# axiom_beta_interface_cmv12000_v0_3.net
KiCad netlist of a schematic drawn in EAGLE
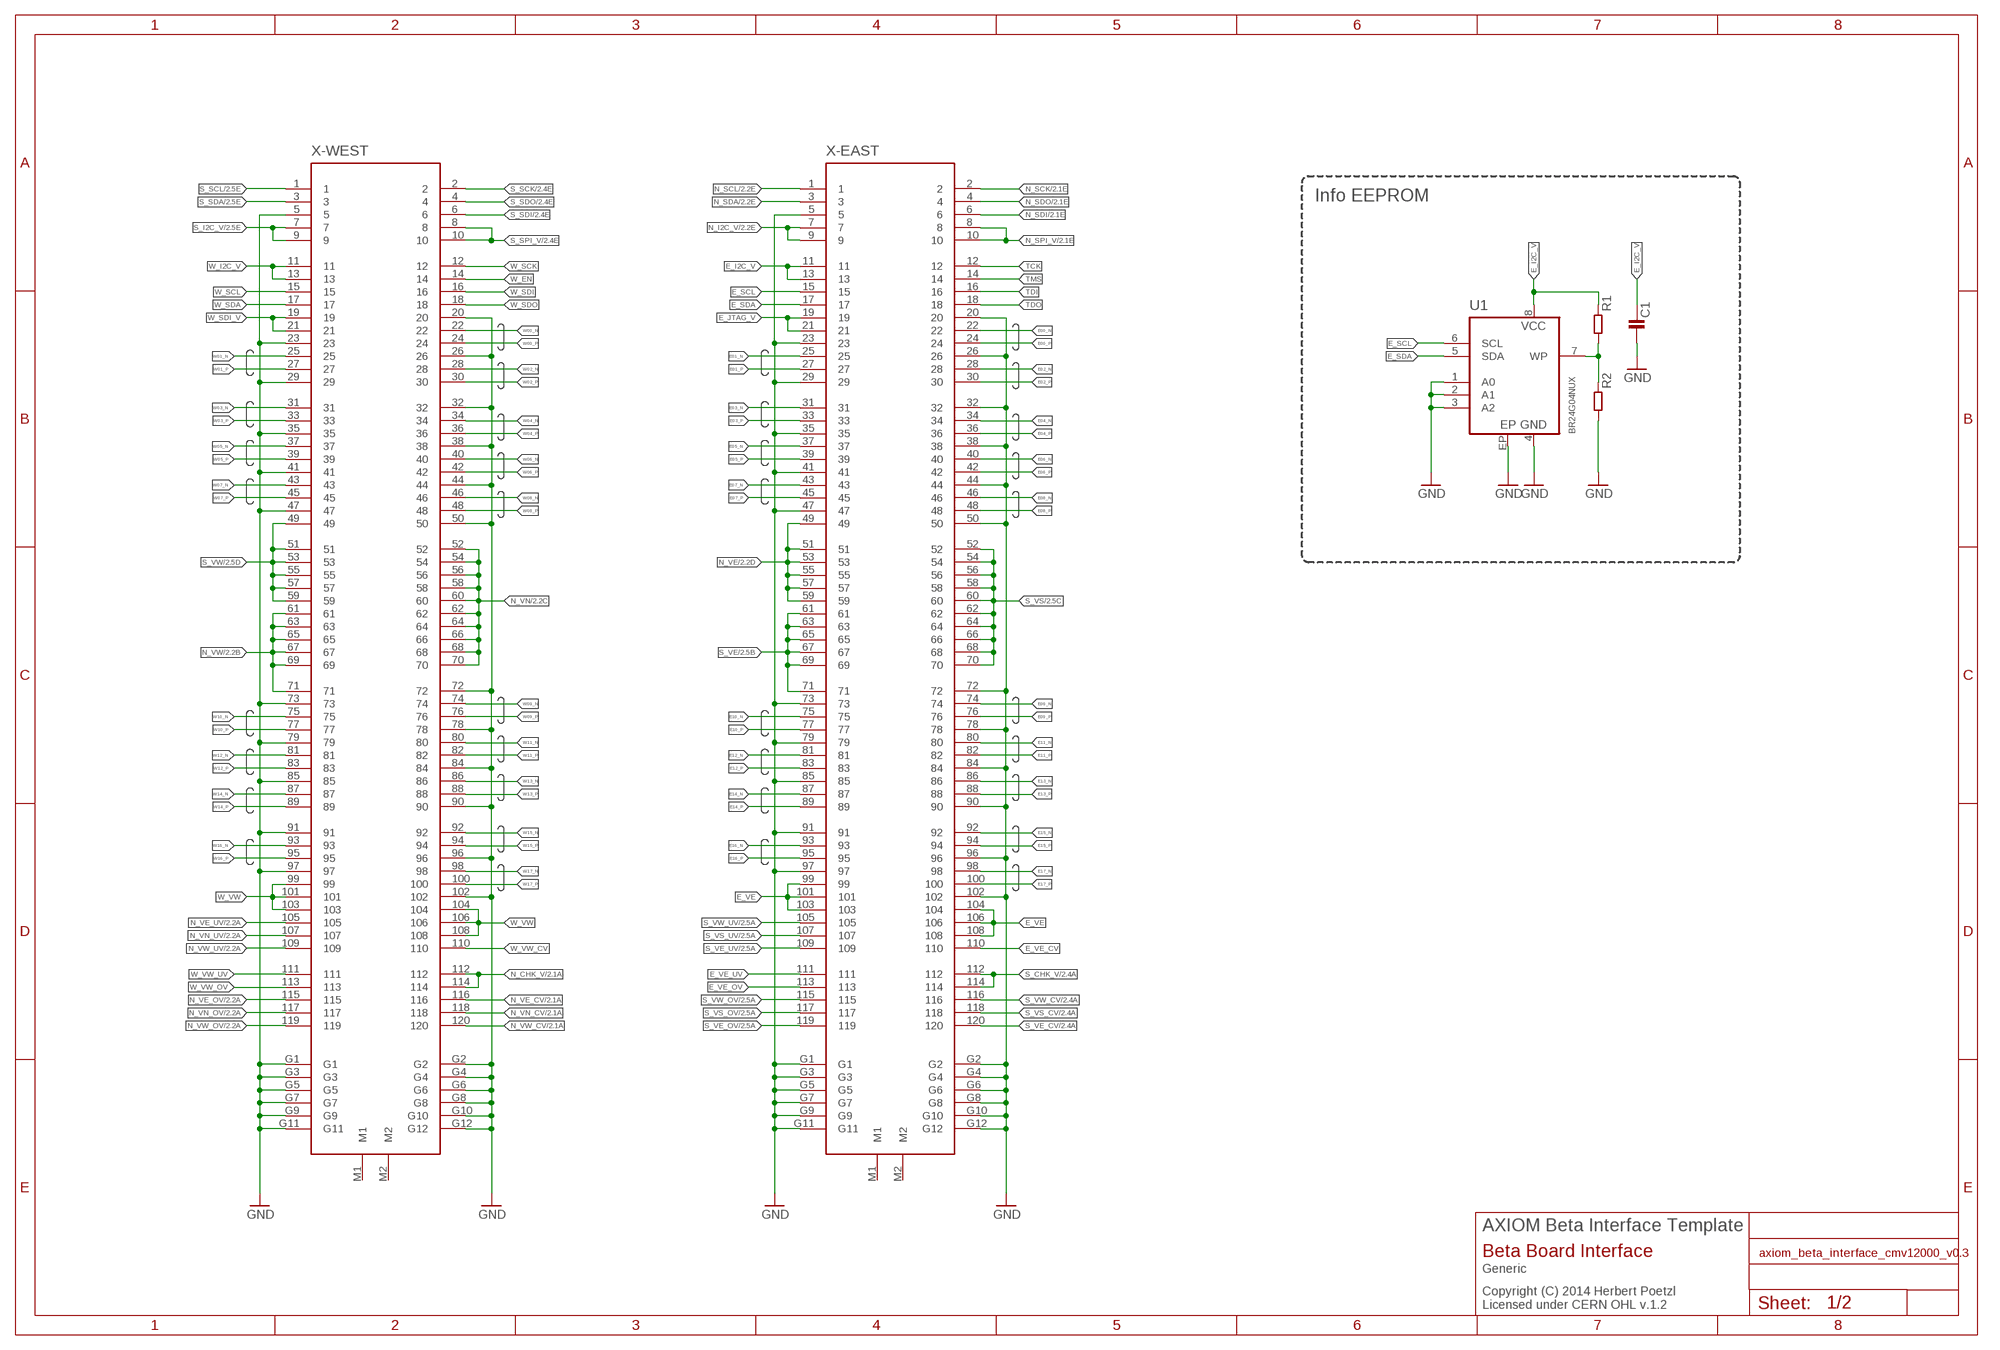
[diagram p0: schematic, sheet 1]
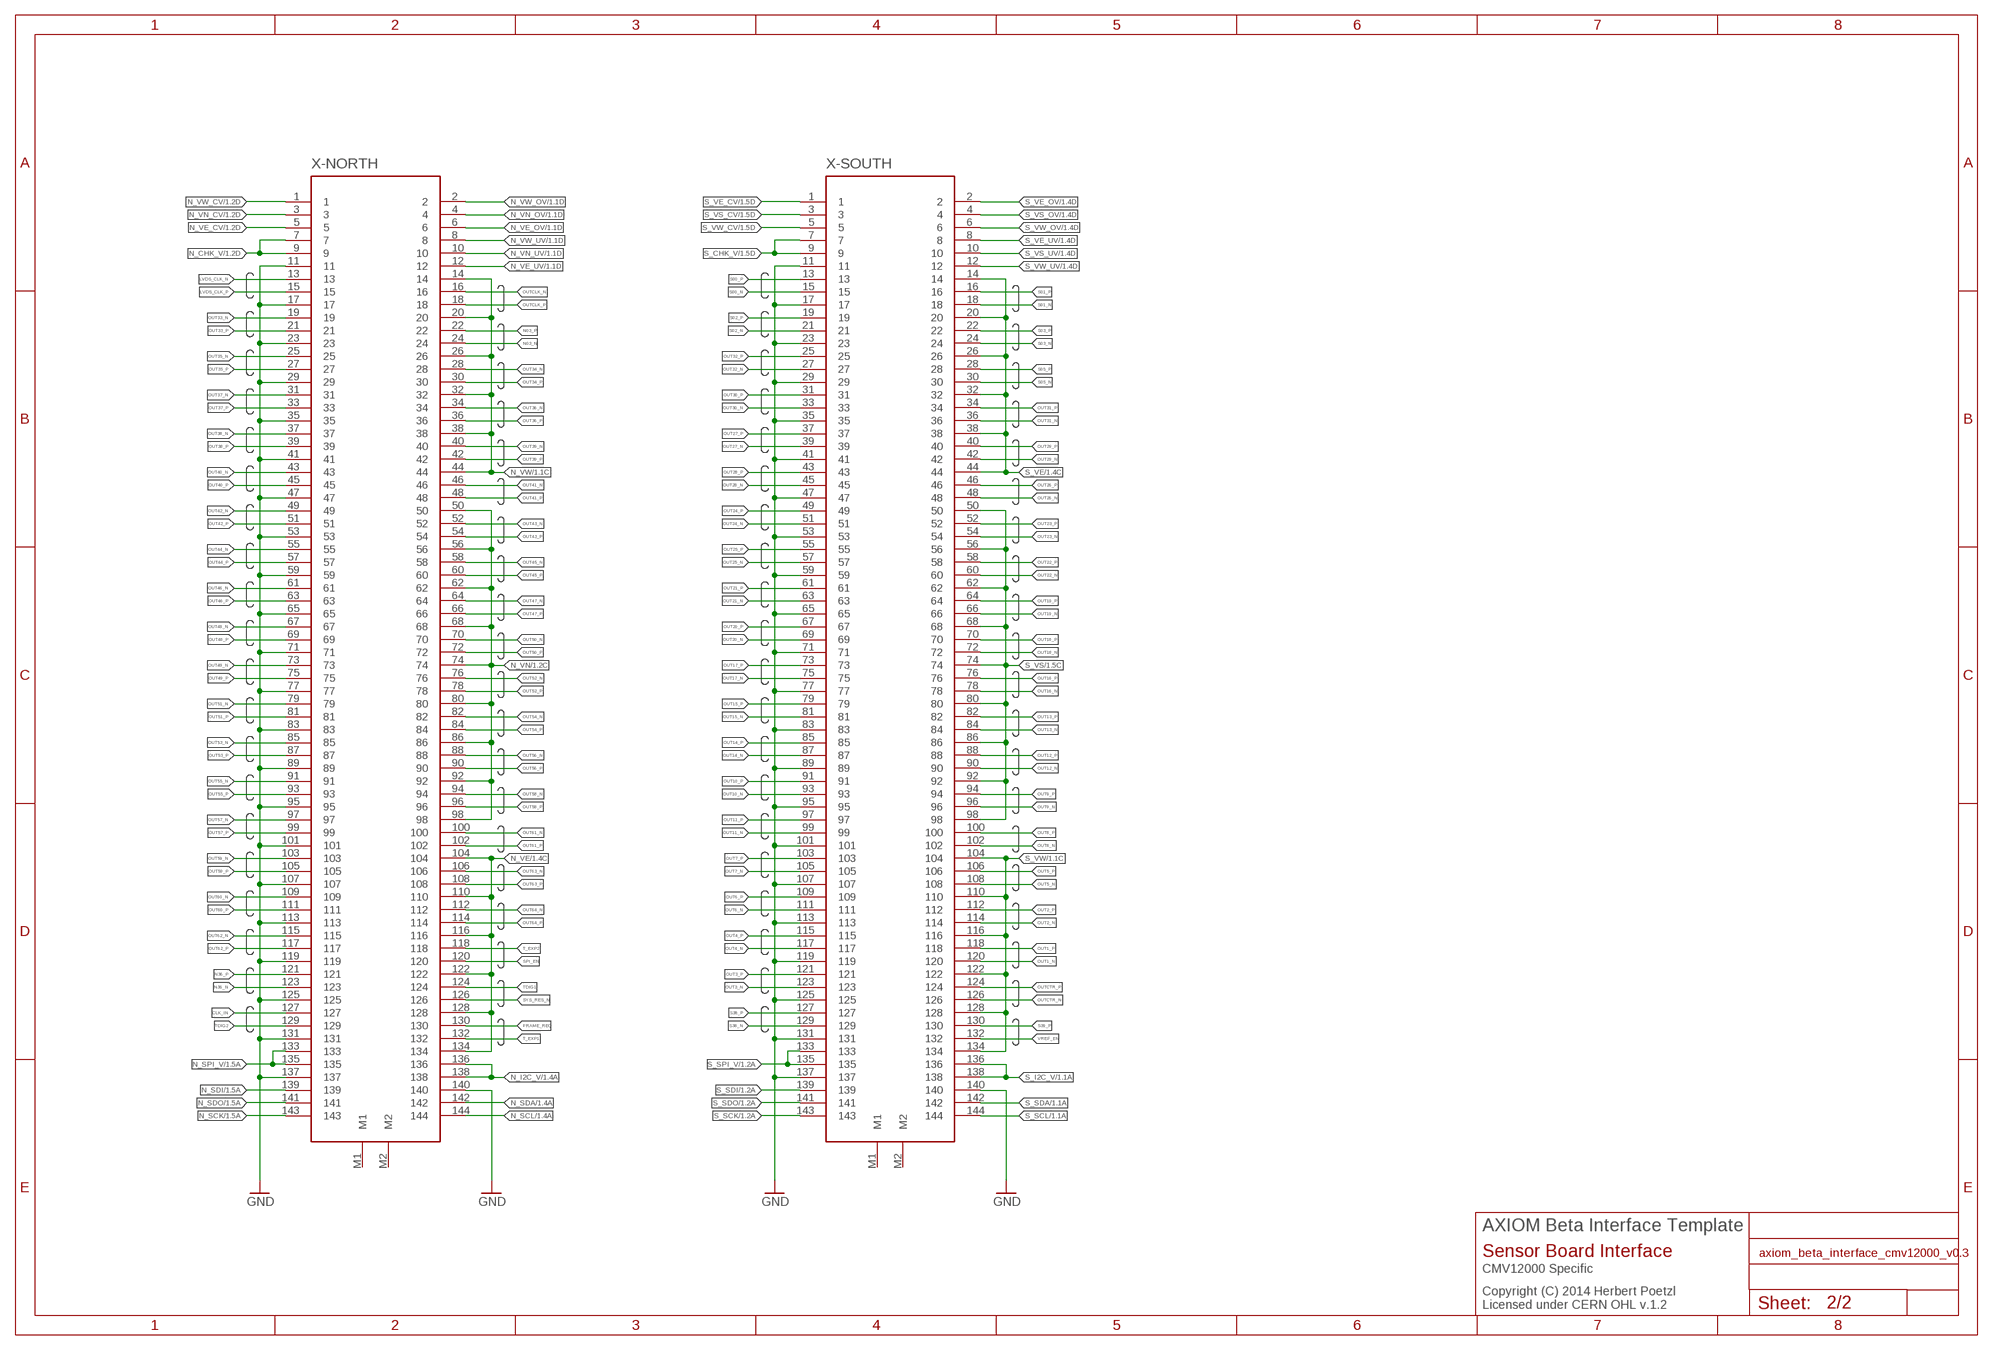
[diagram p1: schematic, sheet 2]

(export (version "E")
  (design (tool "Eeschema 10.0.6"))
  (components
    (comp (ref "X-NORTH")
      (value "FX10-144S")
      (footprint "eagle-import:FX10A-144S")
      (libsource (lib "eagle-import") (part "FX10-144S"))
    )
    (comp (ref "X-SOUTH")
      (value "FX10-144S")
      (footprint "eagle-import:FX10A-144S")
      (libsource (lib "eagle-import") (part "FX10-144S"))
    )
    (comp (ref "C1")
      (value "C0402-B")
      (footprint "eagle-import:0402-B")
      (libsource (lib "eagle-import") (part "C0402-B"))
    )
    (comp (ref "R1")
      (value "R0402-B")
      (footprint "eagle-import:0402-B")
      (libsource (lib "eagle-import") (part "R0402-B"))
    )
    (comp (ref "R2")
      (value "R0402-B")
      (footprint "eagle-import:0402-B")
      (libsource (lib "eagle-import") (part "R0402-B"))
    )
    (comp (ref "U1")
      (value "BR24G04NUX")
      (footprint "eagle-import:DFN200X300X100-9N")
      (libsource (lib "eagle-import") (part "BR24G04NUX"))
    )
    (comp (ref "X-EAST")
      (value "FX10-120/12P")
      (footprint "eagle-import:FX10A-120P_12")
      (libsource (lib "eagle-import") (part "FX10-120/12P"))
    )
    (comp (ref "X-WEST")
      (value "FX10-120/12P")
      (footprint "eagle-import:FX10A-120P_12")
      (libsource (lib "eagle-import") (part "FX10-120/12P"))
    )
  )
  (nets
    (net (code "1") (name "CLK_IN") (class "Default")
      (node (ref "X-NORTH") (pin "127") (pinfunction "127_127") (pintype "bidirectional"))
    )
    (net (code "2") (name "E00_N") (class "Default")
      (node (ref "X-EAST") (pin "22") (pinfunction "22_22") (pintype "bidirectional"))
    )
    (net (code "3") (name "E00_P") (class "Default")
      (node (ref "X-EAST") (pin "24") (pinfunction "24_24") (pintype "bidirectional"))
    )
    (net (code "4") (name "E01_N") (class "Default")
      (node (ref "X-EAST") (pin "25") (pinfunction "25_25") (pintype "bidirectional"))
    )
    (net (code "5") (name "E01_P") (class "Default")
      (node (ref "X-EAST") (pin "27") (pinfunction "27_27") (pintype "bidirectional"))
    )
    (net (code "6") (name "E02_N") (class "Default")
      (node (ref "X-EAST") (pin "28") (pinfunction "28_28") (pintype "bidirectional"))
    )
    (net (code "7") (name "E02_P") (class "Default")
      (node (ref "X-EAST") (pin "30") (pinfunction "30_30") (pintype "bidirectional"))
    )
    (net (code "8") (name "E03_N") (class "Default")
      (node (ref "X-EAST") (pin "31") (pinfunction "31_31") (pintype "bidirectional"))
    )
    (net (code "9") (name "E03_P") (class "Default")
      (node (ref "X-EAST") (pin "33") (pinfunction "33_33") (pintype "bidirectional"))
    )
    (net (code "10") (name "E04_N") (class "Default")
      (node (ref "X-EAST") (pin "34") (pinfunction "34_34") (pintype "bidirectional"))
    )
    (net (code "11") (name "E04_P") (class "Default")
      (node (ref "X-EAST") (pin "36") (pinfunction "36_36") (pintype "bidirectional"))
    )
    (net (code "12") (name "E05_N") (class "Default")
      (node (ref "X-EAST") (pin "37") (pinfunction "37_37") (pintype "bidirectional"))
    )
    (net (code "13") (name "E05_P") (class "Default")
      (node (ref "X-EAST") (pin "39") (pinfunction "39_39") (pintype "bidirectional"))
    )
    (net (code "14") (name "E06_N") (class "Default")
      (node (ref "X-EAST") (pin "40") (pinfunction "40_40") (pintype "bidirectional"))
    )
    (net (code "15") (name "E06_P") (class "Default")
      (node (ref "X-EAST") (pin "42") (pinfunction "42_42") (pintype "bidirectional"))
    )
    (net (code "16") (name "E07_N") (class "Default")
      (node (ref "X-EAST") (pin "43") (pinfunction "43_43") (pintype "bidirectional"))
    )
    (net (code "17") (name "E07_P") (class "Default")
      (node (ref "X-EAST") (pin "45") (pinfunction "45_45") (pintype "bidirectional"))
    )
    (net (code "18") (name "E08_N") (class "Default")
      (node (ref "X-EAST") (pin "46") (pinfunction "46_46") (pintype "bidirectional"))
    )
    (net (code "19") (name "E08_P") (class "Default")
      (node (ref "X-EAST") (pin "48") (pinfunction "48_48") (pintype "bidirectional"))
    )
    (net (code "20") (name "E09_N") (class "Default")
      (node (ref "X-EAST") (pin "74") (pinfunction "74_74") (pintype "bidirectional"))
    )
    (net (code "21") (name "E09_P") (class "Default")
      (node (ref "X-EAST") (pin "76") (pinfunction "76_76") (pintype "bidirectional"))
    )
    (net (code "22") (name "E10_N") (class "Default")
      (node (ref "X-EAST") (pin "75") (pinfunction "75_75") (pintype "bidirectional"))
    )
    (net (code "23") (name "E10_P") (class "Default")
      (node (ref "X-EAST") (pin "77") (pinfunction "77_77") (pintype "bidirectional"))
    )
    (net (code "24") (name "E11_N") (class "Default")
      (node (ref "X-EAST") (pin "80") (pinfunction "80_80") (pintype "bidirectional"))
    )
    (net (code "25") (name "E11_P") (class "Default")
      (node (ref "X-EAST") (pin "82") (pinfunction "82_82") (pintype "bidirectional"))
    )
    (net (code "26") (name "E12_N") (class "Default")
      (node (ref "X-EAST") (pin "81") (pinfunction "81_81") (pintype "bidirectional"))
    )
    (net (code "27") (name "E12_P") (class "Default")
      (node (ref "X-EAST") (pin "83") (pinfunction "83_83") (pintype "bidirectional"))
    )
    (net (code "28") (name "E13_N") (class "Default")
      (node (ref "X-EAST") (pin "86") (pinfunction "86_86") (pintype "bidirectional"))
    )
    (net (code "29") (name "E13_P") (class "Default")
      (node (ref "X-EAST") (pin "88") (pinfunction "88_88") (pintype "bidirectional"))
    )
    (net (code "30") (name "E14_N") (class "Default")
      (node (ref "X-EAST") (pin "87") (pinfunction "87_87") (pintype "bidirectional"))
    )
    (net (code "31") (name "E14_P") (class "Default")
      (node (ref "X-EAST") (pin "89") (pinfunction "89_89") (pintype "bidirectional"))
    )
    (net (code "32") (name "E15_N") (class "Default")
      (node (ref "X-EAST") (pin "92") (pinfunction "92_92") (pintype "bidirectional"))
    )
    (net (code "33") (name "E15_P") (class "Default")
      (node (ref "X-EAST") (pin "94") (pinfunction "94_94") (pintype "bidirectional"))
    )
    (net (code "34") (name "E16_N") (class "Default")
      (node (ref "X-EAST") (pin "93") (pinfunction "93_93") (pintype "bidirectional"))
    )
    (net (code "35") (name "E16_P") (class "Default")
      (node (ref "X-EAST") (pin "95") (pinfunction "95_95") (pintype "bidirectional"))
    )
    (net (code "36") (name "E17_N") (class "Default")
      (node (ref "X-EAST") (pin "98") (pinfunction "98_98") (pintype "bidirectional"))
    )
    (net (code "37") (name "E17_P") (class "Default")
      (node (ref "X-EAST") (pin "100") (pinfunction "100_100") (pintype "bidirectional"))
    )
    (net (code "38") (name "E_I2C_V") (class "Default")
      (node (ref "C1") (pin "1") (pinfunction "1_1") (pintype "passive"))
      (node (ref "R1") (pin "1") (pinfunction "1_1") (pintype "passive"))
      (node (ref "U1") (pin "8") (pinfunction "VCC_8") (pintype "power_in"))
      (node (ref "X-EAST") (pin "11") (pinfunction "11_11") (pintype "bidirectional"))
      (node (ref "X-EAST") (pin "13") (pinfunction "13_13") (pintype "bidirectional"))
    )
    (net (code "39") (name "E_JTAG_V") (class "Default")
      (node (ref "X-EAST") (pin "19") (pinfunction "19_19") (pintype "bidirectional"))
      (node (ref "X-EAST") (pin "21") (pinfunction "21_21") (pintype "bidirectional"))
    )
    (net (code "40") (name "E_SCL") (class "Default")
      (node (ref "U1") (pin "6") (pinfunction "SCL_6") (pintype "input"))
      (node (ref "X-EAST") (pin "15") (pinfunction "15_15") (pintype "bidirectional"))
    )
    (net (code "41") (name "E_SDA") (class "Default")
      (node (ref "U1") (pin "5") (pinfunction "SDA_5") (pintype "bidirectional"))
      (node (ref "X-EAST") (pin "17") (pinfunction "17_17") (pintype "bidirectional"))
    )
    (net (code "42") (name "E_VE") (class "Default")
      (node (ref "X-EAST") (pin "101") (pinfunction "101_101") (pintype "bidirectional"))
      (node (ref "X-EAST") (pin "103") (pinfunction "103_103") (pintype "bidirectional"))
      (node (ref "X-EAST") (pin "104") (pinfunction "104_104") (pintype "bidirectional"))
      (node (ref "X-EAST") (pin "106") (pinfunction "106_106") (pintype "bidirectional"))
      (node (ref "X-EAST") (pin "108") (pinfunction "108_108") (pintype "bidirectional"))
      (node (ref "X-EAST") (pin "99") (pinfunction "99_99") (pintype "bidirectional"))
    )
    (net (code "43") (name "E_VE_CV") (class "Default")
      (node (ref "X-EAST") (pin "110") (pinfunction "110_110") (pintype "bidirectional"))
    )
    (net (code "44") (name "E_VE_OV") (class "Default")
      (node (ref "X-EAST") (pin "113") (pinfunction "113_113") (pintype "bidirectional"))
    )
    (net (code "45") (name "E_VE_UV") (class "Default")
      (node (ref "X-EAST") (pin "111") (pinfunction "111_111") (pintype "bidirectional"))
    )
    (net (code "46") (name "FRAME_REQ") (class "Default")
      (node (ref "X-NORTH") (pin "130") (pinfunction "130_130") (pintype "bidirectional"))
    )
    (net (code "47") (name "GND") (class "Default")
      (node (ref "C1") (pin "2") (pinfunction "2_2") (pintype "passive"))
      (node (ref "R2") (pin "2") (pinfunction "2_2") (pintype "passive"))
      (node (ref "U1") (pin "1") (pinfunction "A0_1") (pintype "input"))
      (node (ref "U1") (pin "2") (pinfunction "A1_2") (pintype "input"))
      (node (ref "U1") (pin "3") (pinfunction "A2_3") (pintype "input"))
      (node (ref "U1") (pin "4") (pinfunction "GND_4") (pintype "passive"))
      (node (ref "U1") (pin "EP") (pinfunction "EP_EP") (pintype "passive"))
      (node (ref "X-EAST") (pin "102") (pinfunction "102_102") (pintype "bidirectional"))
      (node (ref "X-EAST") (pin "20") (pinfunction "20_20") (pintype "bidirectional"))
      (node (ref "X-EAST") (pin "23") (pinfunction "23_23") (pintype "bidirectional"))
      (node (ref "X-EAST") (pin "26") (pinfunction "26_26") (pintype "bidirectional"))
      (node (ref "X-EAST") (pin "29") (pinfunction "29_29") (pintype "bidirectional"))
      (node (ref "X-EAST") (pin "32") (pinfunction "32_32") (pintype "bidirectional"))
      (node (ref "X-EAST") (pin "35") (pinfunction "35_35") (pintype "bidirectional"))
      (node (ref "X-EAST") (pin "38") (pinfunction "38_38") (pintype "bidirectional"))
      (node (ref "X-EAST") (pin "41") (pinfunction "41_41") (pintype "bidirectional"))
      (node (ref "X-EAST") (pin "44") (pinfunction "44_44") (pintype "bidirectional"))
      (node (ref "X-EAST") (pin "47") (pinfunction "47_47") (pintype "bidirectional"))
      (node (ref "X-EAST") (pin "5") (pinfunction "5_5") (pintype "bidirectional"))
      (node (ref "X-EAST") (pin "50") (pinfunction "50_50") (pintype "bidirectional"))
      (node (ref "X-EAST") (pin "72") (pinfunction "72_72") (pintype "bidirectional"))
      (node (ref "X-EAST") (pin "73") (pinfunction "73_73") (pintype "bidirectional"))
      (node (ref "X-EAST") (pin "78") (pinfunction "78_78") (pintype "bidirectional"))
      (node (ref "X-EAST") (pin "79") (pinfunction "79_79") (pintype "bidirectional"))
      (node (ref "X-EAST") (pin "84") (pinfunction "84_84") (pintype "bidirectional"))
      (node (ref "X-EAST") (pin "85") (pinfunction "85_85") (pintype "bidirectional"))
      (node (ref "X-EAST") (pin "90") (pinfunction "90_90") (pintype "bidirectional"))
      (node (ref "X-EAST") (pin "91") (pinfunction "91_91") (pintype "bidirectional"))
      (node (ref "X-EAST") (pin "96") (pinfunction "96_96") (pintype "bidirectional"))
      (node (ref "X-EAST") (pin "97") (pinfunction "97_97") (pintype "bidirectional"))
      (node (ref "X-EAST") (pin "G1") (pinfunction "G1_G1") (pintype "bidirectional"))
      (node (ref "X-EAST") (pin "G10") (pinfunction "G10_G10") (pintype "bidirectional"))
      (node (ref "X-EAST") (pin "G11") (pinfunction "G11_G11") (pintype "bidirectional"))
      (node (ref "X-EAST") (pin "G12") (pinfunction "G12_G12") (pintype "bidirectional"))
      (node (ref "X-EAST") (pin "G2") (pinfunction "G2_G2") (pintype "bidirectional"))
      (node (ref "X-EAST") (pin "G3") (pinfunction "G3_G3") (pintype "bidirectional"))
      (node (ref "X-EAST") (pin "G4") (pinfunction "G4_G4") (pintype "bidirectional"))
      (node (ref "X-EAST") (pin "G5") (pinfunction "G5_G5") (pintype "bidirectional"))
      (node (ref "X-EAST") (pin "G6") (pinfunction "G6_G6") (pintype "bidirectional"))
      (node (ref "X-EAST") (pin "G7") (pinfunction "G7_G7") (pintype "bidirectional"))
      (node (ref "X-EAST") (pin "G8") (pinfunction "G8_G8") (pintype "bidirectional"))
      (node (ref "X-EAST") (pin "G9") (pinfunction "G9_G9") (pintype "bidirectional"))
      (node (ref "X-NORTH") (pin "101") (pinfunction "101_101") (pintype "bidirectional"))
      (node (ref "X-NORTH") (pin "107") (pinfunction "107_107") (pintype "bidirectional"))
      (node (ref "X-NORTH") (pin "11") (pinfunction "11_11") (pintype "bidirectional"))
      (node (ref "X-NORTH") (pin "113") (pinfunction "113_113") (pintype "bidirectional"))
      (node (ref "X-NORTH") (pin "119") (pinfunction "119_119") (pintype "bidirectional"))
      (node (ref "X-NORTH") (pin "125") (pinfunction "125_125") (pintype "bidirectional"))
      (node (ref "X-NORTH") (pin "131") (pinfunction "131_131") (pintype "bidirectional"))
      (node (ref "X-NORTH") (pin "137") (pinfunction "137_137") (pintype "bidirectional"))
      (node (ref "X-NORTH") (pin "140") (pinfunction "140_140") (pintype "bidirectional"))
      (node (ref "X-NORTH") (pin "17") (pinfunction "17_17") (pintype "bidirectional"))
      (node (ref "X-NORTH") (pin "23") (pinfunction "23_23") (pintype "bidirectional"))
      (node (ref "X-NORTH") (pin "29") (pinfunction "29_29") (pintype "bidirectional"))
      (node (ref "X-NORTH") (pin "35") (pinfunction "35_35") (pintype "bidirectional"))
      (node (ref "X-NORTH") (pin "41") (pinfunction "41_41") (pintype "bidirectional"))
      (node (ref "X-NORTH") (pin "47") (pinfunction "47_47") (pintype "bidirectional"))
      (node (ref "X-NORTH") (pin "53") (pinfunction "53_53") (pintype "bidirectional"))
      (node (ref "X-NORTH") (pin "59") (pinfunction "59_59") (pintype "bidirectional"))
      (node (ref "X-NORTH") (pin "65") (pinfunction "65_65") (pintype "bidirectional"))
      (node (ref "X-NORTH") (pin "71") (pinfunction "71_71") (pintype "bidirectional"))
      (node (ref "X-NORTH") (pin "77") (pinfunction "77_77") (pintype "bidirectional"))
      (node (ref "X-NORTH") (pin "83") (pinfunction "83_83") (pintype "bidirectional"))
      (node (ref "X-NORTH") (pin "89") (pinfunction "89_89") (pintype "bidirectional"))
      (node (ref "X-NORTH") (pin "95") (pinfunction "95_95") (pintype "bidirectional"))
      (node (ref "X-SOUTH") (pin "101") (pinfunction "101_101") (pintype "bidirectional"))
      (node (ref "X-SOUTH") (pin "107") (pinfunction "107_107") (pintype "bidirectional"))
      (node (ref "X-SOUTH") (pin "11") (pinfunction "11_11") (pintype "bidirectional"))
      (node (ref "X-SOUTH") (pin "113") (pinfunction "113_113") (pintype "bidirectional"))
      (node (ref "X-SOUTH") (pin "119") (pinfunction "119_119") (pintype "bidirectional"))
      (node (ref "X-SOUTH") (pin "125") (pinfunction "125_125") (pintype "bidirectional"))
      (node (ref "X-SOUTH") (pin "131") (pinfunction "131_131") (pintype "bidirectional"))
      (node (ref "X-SOUTH") (pin "137") (pinfunction "137_137") (pintype "bidirectional"))
      (node (ref "X-SOUTH") (pin "140") (pinfunction "140_140") (pintype "bidirectional"))
      (node (ref "X-SOUTH") (pin "17") (pinfunction "17_17") (pintype "bidirectional"))
      (node (ref "X-SOUTH") (pin "23") (pinfunction "23_23") (pintype "bidirectional"))
      (node (ref "X-SOUTH") (pin "29") (pinfunction "29_29") (pintype "bidirectional"))
      (node (ref "X-SOUTH") (pin "35") (pinfunction "35_35") (pintype "bidirectional"))
      (node (ref "X-SOUTH") (pin "41") (pinfunction "41_41") (pintype "bidirectional"))
      (node (ref "X-SOUTH") (pin "47") (pinfunction "47_47") (pintype "bidirectional"))
      (node (ref "X-SOUTH") (pin "53") (pinfunction "53_53") (pintype "bidirectional"))
      (node (ref "X-SOUTH") (pin "59") (pinfunction "59_59") (pintype "bidirectional"))
      (node (ref "X-SOUTH") (pin "65") (pinfunction "65_65") (pintype "bidirectional"))
      (node (ref "X-SOUTH") (pin "71") (pinfunction "71_71") (pintype "bidirectional"))
      (node (ref "X-SOUTH") (pin "77") (pinfunction "77_77") (pintype "bidirectional"))
      (node (ref "X-SOUTH") (pin "83") (pinfunction "83_83") (pintype "bidirectional"))
      (node (ref "X-SOUTH") (pin "89") (pinfunction "89_89") (pintype "bidirectional"))
      (node (ref "X-SOUTH") (pin "95") (pinfunction "95_95") (pintype "bidirectional"))
      (node (ref "X-WEST") (pin "102") (pinfunction "102_102") (pintype "bidirectional"))
      (node (ref "X-WEST") (pin "20") (pinfunction "20_20") (pintype "bidirectional"))
      (node (ref "X-WEST") (pin "23") (pinfunction "23_23") (pintype "bidirectional"))
      (node (ref "X-WEST") (pin "26") (pinfunction "26_26") (pintype "bidirectional"))
      (node (ref "X-WEST") (pin "29") (pinfunction "29_29") (pintype "bidirectional"))
      (node (ref "X-WEST") (pin "32") (pinfunction "32_32") (pintype "bidirectional"))
      (node (ref "X-WEST") (pin "35") (pinfunction "35_35") (pintype "bidirectional"))
      (node (ref "X-WEST") (pin "38") (pinfunction "38_38") (pintype "bidirectional"))
      (node (ref "X-WEST") (pin "41") (pinfunction "41_41") (pintype "bidirectional"))
      (node (ref "X-WEST") (pin "44") (pinfunction "44_44") (pintype "bidirectional"))
      (node (ref "X-WEST") (pin "47") (pinfunction "47_47") (pintype "bidirectional"))
      (node (ref "X-WEST") (pin "5") (pinfunction "5_5") (pintype "bidirectional"))
      (node (ref "X-WEST") (pin "50") (pinfunction "50_50") (pintype "bidirectional"))
      (node (ref "X-WEST") (pin "72") (pinfunction "72_72") (pintype "bidirectional"))
      (node (ref "X-WEST") (pin "73") (pinfunction "73_73") (pintype "bidirectional"))
      (node (ref "X-WEST") (pin "78") (pinfunction "78_78") (pintype "bidirectional"))
      (node (ref "X-WEST") (pin "79") (pinfunction "79_79") (pintype "bidirectional"))
      (node (ref "X-WEST") (pin "84") (pinfunction "84_84") (pintype "bidirectional"))
      (node (ref "X-WEST") (pin "85") (pinfunction "85_85") (pintype "bidirectional"))
      (node (ref "X-WEST") (pin "90") (pinfunction "90_90") (pintype "bidirectional"))
      (node (ref "X-WEST") (pin "91") (pinfunction "91_91") (pintype "bidirectional"))
      (node (ref "X-WEST") (pin "96") (pinfunction "96_96") (pintype "bidirectional"))
      (node (ref "X-WEST") (pin "97") (pinfunction "97_97") (pintype "bidirectional"))
      (node (ref "X-WEST") (pin "G1") (pinfunction "G1_G1") (pintype "bidirectional"))
      (node (ref "X-WEST") (pin "G10") (pinfunction "G10_G10") (pintype "bidirectional"))
      (node (ref "X-WEST") (pin "G11") (pinfunction "G11_G11") (pintype "bidirectional"))
      (node (ref "X-WEST") (pin "G12") (pinfunction "G12_G12") (pintype "bidirectional"))
      (node (ref "X-WEST") (pin "G2") (pinfunction "G2_G2") (pintype "bidirectional"))
      (node (ref "X-WEST") (pin "G3") (pinfunction "G3_G3") (pintype "bidirectional"))
      (node (ref "X-WEST") (pin "G4") (pinfunction "G4_G4") (pintype "bidirectional"))
      (node (ref "X-WEST") (pin "G5") (pinfunction "G5_G5") (pintype "bidirectional"))
      (node (ref "X-WEST") (pin "G6") (pinfunction "G6_G6") (pintype "bidirectional"))
      (node (ref "X-WEST") (pin "G7") (pinfunction "G7_G7") (pintype "bidirectional"))
      (node (ref "X-WEST") (pin "G8") (pinfunction "G8_G8") (pintype "bidirectional"))
      (node (ref "X-WEST") (pin "G9") (pinfunction "G9_G9") (pintype "bidirectional"))
    )
    (net (code "48") (name "LVDS_CLK_N") (class "Default")
      (node (ref "X-NORTH") (pin "13") (pinfunction "13_13") (pintype "bidirectional"))
    )
    (net (code "49") (name "LVDS_CLK_P") (class "Default")
      (node (ref "X-NORTH") (pin "15") (pinfunction "15_15") (pintype "bidirectional"))
    )
    (net (code "50") (name "N03_N") (class "Default")
      (node (ref "X-NORTH") (pin "24") (pinfunction "24_24") (pintype "bidirectional"))
    )
    (net (code "51") (name "N03_P") (class "Default")
      (node (ref "X-NORTH") (pin "22") (pinfunction "22_22") (pintype "bidirectional"))
    )
    (net (code "52") (name "N36_N") (class "Default")
      (node (ref "X-NORTH") (pin "123") (pinfunction "123_123") (pintype "bidirectional"))
    )
    (net (code "53") (name "N36_P") (class "Default")
      (node (ref "X-NORTH") (pin "121") (pinfunction "121_121") (pintype "bidirectional"))
    )
    (net (code "54") (name "N_CHK_V") (class "Default")
      (node (ref "X-NORTH") (pin "7") (pinfunction "7_7") (pintype "bidirectional"))
      (node (ref "X-NORTH") (pin "9") (pinfunction "9_9") (pintype "bidirectional"))
      (node (ref "X-WEST") (pin "112") (pinfunction "112_112") (pintype "bidirectional"))
      (node (ref "X-WEST") (pin "114") (pinfunction "114_114") (pintype "bidirectional"))
    )
    (net (code "55") (name "N_I2C_V") (class "Default")
      (node (ref "X-EAST") (pin "7") (pinfunction "7_7") (pintype "bidirectional"))
      (node (ref "X-EAST") (pin "9") (pinfunction "9_9") (pintype "bidirectional"))
      (node (ref "X-NORTH") (pin "136") (pinfunction "136_136") (pintype "bidirectional"))
      (node (ref "X-NORTH") (pin "138") (pinfunction "138_138") (pintype "bidirectional"))
    )
    (net (code "56") (name "N_SCK") (class "Default")
      (node (ref "X-EAST") (pin "2") (pinfunction "2_2") (pintype "bidirectional"))
      (node (ref "X-NORTH") (pin "143") (pinfunction "143_143") (pintype "bidirectional"))
    )
    (net (code "57") (name "N_SCL") (class "Default")
      (node (ref "X-EAST") (pin "1") (pinfunction "1_1") (pintype "bidirectional"))
      (node (ref "X-NORTH") (pin "144") (pinfunction "144_144") (pintype "bidirectional"))
    )
    (net (code "58") (name "N_SDA") (class "Default")
      (node (ref "X-EAST") (pin "3") (pinfunction "3_3") (pintype "bidirectional"))
      (node (ref "X-NORTH") (pin "142") (pinfunction "142_142") (pintype "bidirectional"))
    )
    (net (code "59") (name "N_SDI") (class "Default")
      (node (ref "X-EAST") (pin "6") (pinfunction "6_6") (pintype "bidirectional"))
      (node (ref "X-NORTH") (pin "139") (pinfunction "139_139") (pintype "bidirectional"))
    )
    (net (code "60") (name "N_SDO") (class "Default")
      (node (ref "X-EAST") (pin "4") (pinfunction "4_4") (pintype "bidirectional"))
      (node (ref "X-NORTH") (pin "141") (pinfunction "141_141") (pintype "bidirectional"))
    )
    (net (code "61") (name "N_SPI_V") (class "Default")
      (node (ref "X-EAST") (pin "10") (pinfunction "10_10") (pintype "bidirectional"))
      (node (ref "X-EAST") (pin "8") (pinfunction "8_8") (pintype "bidirectional"))
      (node (ref "X-NORTH") (pin "133") (pinfunction "133_133") (pintype "bidirectional"))
      (node (ref "X-NORTH") (pin "135") (pinfunction "135_135") (pintype "bidirectional"))
    )
    (net (code "62") (name "N_VE") (class "Default")
      (node (ref "X-EAST") (pin "49") (pinfunction "49_49") (pintype "bidirectional"))
      (node (ref "X-EAST") (pin "51") (pinfunction "51_51") (pintype "bidirectional"))
      (node (ref "X-EAST") (pin "53") (pinfunction "53_53") (pintype "bidirectional"))
      (node (ref "X-EAST") (pin "55") (pinfunction "55_55") (pintype "bidirectional"))
      (node (ref "X-EAST") (pin "57") (pinfunction "57_57") (pintype "bidirectional"))
      (node (ref "X-EAST") (pin "59") (pinfunction "59_59") (pintype "bidirectional"))
      (node (ref "X-NORTH") (pin "104") (pinfunction "104_104") (pintype "bidirectional"))
      (node (ref "X-NORTH") (pin "110") (pinfunction "110_110") (pintype "bidirectional"))
      (node (ref "X-NORTH") (pin "116") (pinfunction "116_116") (pintype "bidirectional"))
      (node (ref "X-NORTH") (pin "122") (pinfunction "122_122") (pintype "bidirectional"))
      (node (ref "X-NORTH") (pin "128") (pinfunction "128_128") (pintype "bidirectional"))
      (node (ref "X-NORTH") (pin "134") (pinfunction "134_134") (pintype "bidirectional"))
    )
    (net (code "63") (name "N_VE_CV") (class "Default")
      (node (ref "X-NORTH") (pin "5") (pinfunction "5_5") (pintype "bidirectional"))
      (node (ref "X-WEST") (pin "116") (pinfunction "116_116") (pintype "bidirectional"))
    )
    (net (code "64") (name "N_VE_OV") (class "Default")
      (node (ref "X-NORTH") (pin "6") (pinfunction "6_6") (pintype "bidirectional"))
      (node (ref "X-WEST") (pin "115") (pinfunction "115_115") (pintype "bidirectional"))
    )
    (net (code "65") (name "N_VE_UV") (class "Default")
      (node (ref "X-NORTH") (pin "12") (pinfunction "12_12") (pintype "bidirectional"))
      (node (ref "X-WEST") (pin "105") (pinfunction "105_105") (pintype "bidirectional"))
    )
    (net (code "66") (name "N_VN") (class "Default")
      (node (ref "X-NORTH") (pin "50") (pinfunction "50_50") (pintype "bidirectional"))
      (node (ref "X-NORTH") (pin "56") (pinfunction "56_56") (pintype "bidirectional"))
      (node (ref "X-NORTH") (pin "62") (pinfunction "62_62") (pintype "bidirectional"))
      (node (ref "X-NORTH") (pin "68") (pinfunction "68_68") (pintype "bidirectional"))
      (node (ref "X-NORTH") (pin "74") (pinfunction "74_74") (pintype "bidirectional"))
      (node (ref "X-NORTH") (pin "80") (pinfunction "80_80") (pintype "bidirectional"))
      (node (ref "X-NORTH") (pin "86") (pinfunction "86_86") (pintype "bidirectional"))
      (node (ref "X-NORTH") (pin "92") (pinfunction "92_92") (pintype "bidirectional"))
      (node (ref "X-NORTH") (pin "98") (pinfunction "98_98") (pintype "bidirectional"))
      (node (ref "X-WEST") (pin "52") (pinfunction "52_52") (pintype "bidirectional"))
      (node (ref "X-WEST") (pin "54") (pinfunction "54_54") (pintype "bidirectional"))
      (node (ref "X-WEST") (pin "56") (pinfunction "56_56") (pintype "bidirectional"))
      (node (ref "X-WEST") (pin "58") (pinfunction "58_58") (pintype "bidirectional"))
      (node (ref "X-WEST") (pin "60") (pinfunction "60_60") (pintype "bidirectional"))
      (node (ref "X-WEST") (pin "62") (pinfunction "62_62") (pintype "bidirectional"))
      (node (ref "X-WEST") (pin "64") (pinfunction "64_64") (pintype "bidirectional"))
      (node (ref "X-WEST") (pin "66") (pinfunction "66_66") (pintype "bidirectional"))
      (node (ref "X-WEST") (pin "68") (pinfunction "68_68") (pintype "bidirectional"))
      (node (ref "X-WEST") (pin "70") (pinfunction "70_70") (pintype "bidirectional"))
    )
    (net (code "67") (name "N_VN_CV") (class "Default")
      (node (ref "X-NORTH") (pin "3") (pinfunction "3_3") (pintype "bidirectional"))
      (node (ref "X-WEST") (pin "118") (pinfunction "118_118") (pintype "bidirectional"))
    )
    (net (code "68") (name "N_VN_OV") (class "Default")
      (node (ref "X-NORTH") (pin "4") (pinfunction "4_4") (pintype "bidirectional"))
      (node (ref "X-WEST") (pin "117") (pinfunction "117_117") (pintype "bidirectional"))
    )
    (net (code "69") (name "N_VN_UV") (class "Default")
      (node (ref "X-NORTH") (pin "10") (pinfunction "10_10") (pintype "bidirectional"))
      (node (ref "X-WEST") (pin "107") (pinfunction "107_107") (pintype "bidirectional"))
    )
    (net (code "70") (name "N_VW") (class "Default")
      (node (ref "X-NORTH") (pin "14") (pinfunction "14_14") (pintype "bidirectional"))
      (node (ref "X-NORTH") (pin "20") (pinfunction "20_20") (pintype "bidirectional"))
      (node (ref "X-NORTH") (pin "26") (pinfunction "26_26") (pintype "bidirectional"))
      (node (ref "X-NORTH") (pin "32") (pinfunction "32_32") (pintype "bidirectional"))
      (node (ref "X-NORTH") (pin "38") (pinfunction "38_38") (pintype "bidirectional"))
      (node (ref "X-NORTH") (pin "44") (pinfunction "44_44") (pintype "bidirectional"))
      (node (ref "X-WEST") (pin "61") (pinfunction "61_61") (pintype "bidirectional"))
      (node (ref "X-WEST") (pin "63") (pinfunction "63_63") (pintype "bidirectional"))
      (node (ref "X-WEST") (pin "65") (pinfunction "65_65") (pintype "bidirectional"))
      (node (ref "X-WEST") (pin "67") (pinfunction "67_67") (pintype "bidirectional"))
      (node (ref "X-WEST") (pin "69") (pinfunction "69_69") (pintype "bidirectional"))
      (node (ref "X-WEST") (pin "71") (pinfunction "71_71") (pintype "bidirectional"))
    )
    (net (code "71") (name "N_VW_CV") (class "Default")
      (node (ref "X-NORTH") (pin "1") (pinfunction "1_1") (pintype "bidirectional"))
      (node (ref "X-WEST") (pin "120") (pinfunction "120_120") (pintype "bidirectional"))
    )
    (net (code "72") (name "N_VW_OV") (class "Default")
      (node (ref "X-NORTH") (pin "2") (pinfunction "2_2") (pintype "bidirectional"))
      (node (ref "X-WEST") (pin "119") (pinfunction "119_119") (pintype "bidirectional"))
    )
    (net (code "73") (name "N_VW_UV") (class "Default")
      (node (ref "X-NORTH") (pin "8") (pinfunction "8_8") (pintype "bidirectional"))
      (node (ref "X-WEST") (pin "109") (pinfunction "109_109") (pintype "bidirectional"))
    )
    (net (code "74") (name "Net-(U1-WP)") (class "Default")
      (node (ref "R1") (pin "2") (pinfunction "2_2") (pintype "passive"))
      (node (ref "R2") (pin "1") (pinfunction "1_1") (pintype "passive"))
      (node (ref "U1") (pin "7") (pinfunction "WP_7") (pintype "input"))
    )
    (net (code "75") (name "OUT1_N") (class "Default")
      (node (ref "X-SOUTH") (pin "120") (pinfunction "120_120") (pintype "bidirectional"))
    )
    (net (code "76") (name "OUT1_P") (class "Default")
      (node (ref "X-SOUTH") (pin "118") (pinfunction "118_118") (pintype "bidirectional"))
    )
    (net (code "77") (name "OUT2_N") (class "Default")
      (node (ref "X-SOUTH") (pin "114") (pinfunction "114_114") (pintype "bidirectional"))
    )
    (net (code "78") (name "OUT2_P") (class "Default")
      (node (ref "X-SOUTH") (pin "112") (pinfunction "112_112") (pintype "bidirectional"))
    )
    (net (code "79") (name "OUT3_N") (class "Default")
      (node (ref "X-SOUTH") (pin "123") (pinfunction "123_123") (pintype "bidirectional"))
    )
    (net (code "80") (name "OUT3_P") (class "Default")
      (node (ref "X-SOUTH") (pin "121") (pinfunction "121_121") (pintype "bidirectional"))
    )
    (net (code "81") (name "OUT4_N") (class "Default")
      (node (ref "X-SOUTH") (pin "117") (pinfunction "117_117") (pintype "bidirectional"))
    )
    (net (code "82") (name "OUT4_P") (class "Default")
      (node (ref "X-SOUTH") (pin "115") (pinfunction "115_115") (pintype "bidirectional"))
    )
    (net (code "83") (name "OUT5_N") (class "Default")
      (node (ref "X-SOUTH") (pin "108") (pinfunction "108_108") (pintype "bidirectional"))
    )
    (net (code "84") (name "OUT5_P") (class "Default")
      (node (ref "X-SOUTH") (pin "106") (pinfunction "106_106") (pintype "bidirectional"))
    )
    (net (code "85") (name "OUT6_N") (class "Default")
      (node (ref "X-SOUTH") (pin "111") (pinfunction "111_111") (pintype "bidirectional"))
    )
    (net (code "86") (name "OUT6_P") (class "Default")
      (node (ref "X-SOUTH") (pin "109") (pinfunction "109_109") (pintype "bidirectional"))
    )
    (net (code "87") (name "OUT7_N") (class "Default")
      (node (ref "X-SOUTH") (pin "105") (pinfunction "105_105") (pintype "bidirectional"))
    )
    (net (code "88") (name "OUT7_P") (class "Default")
      (node (ref "X-SOUTH") (pin "103") (pinfunction "103_103") (pintype "bidirectional"))
    )
    (net (code "89") (name "OUT8_N") (class "Default")
      (node (ref "X-SOUTH") (pin "102") (pinfunction "102_102") (pintype "bidirectional"))
    )
    (net (code "90") (name "OUT8_P") (class "Default")
      (node (ref "X-SOUTH") (pin "100") (pinfunction "100_100") (pintype "bidirectional"))
    )
    (net (code "91") (name "OUT9_N") (class "Default")
      (node (ref "X-SOUTH") (pin "96") (pinfunction "96_96") (pintype "bidirectional"))
    )
    (net (code "92") (name "OUT9_P") (class "Default")
      (node (ref "X-SOUTH") (pin "94") (pinfunction "94_94") (pintype "bidirectional"))
    )
    (net (code "93") (name "OUT10_N") (class "Default")
      (node (ref "X-SOUTH") (pin "93") (pinfunction "93_93") (pintype "bidirectional"))
    )
    (net (code "94") (name "OUT10_P") (class "Default")
      (node (ref "X-SOUTH") (pin "91") (pinfunction "91_91") (pintype "bidirectional"))
    )
    (net (code "95") (name "OUT11_N") (class "Default")
      (node (ref "X-SOUTH") (pin "99") (pinfunction "99_99") (pintype "bidirectional"))
    )
    (net (code "96") (name "OUT11_P") (class "Default")
      (node (ref "X-SOUTH") (pin "97") (pinfunction "97_97") (pintype "bidirectional"))
    )
    (net (code "97") (name "OUT12_N") (class "Default")
      (node (ref "X-SOUTH") (pin "90") (pinfunction "90_90") (pintype "bidirectional"))
    )
    (net (code "98") (name "OUT12_P") (class "Default")
      (node (ref "X-SOUTH") (pin "88") (pinfunction "88_88") (pintype "bidirectional"))
    )
    (net (code "99") (name "OUT13_N") (class "Default")
      (node (ref "X-SOUTH") (pin "84") (pinfunction "84_84") (pintype "bidirectional"))
    )
    (net (code "100") (name "OUT13_P") (class "Default")
      (node (ref "X-SOUTH") (pin "82") (pinfunction "82_82") (pintype "bidirectional"))
    )
    (net (code "101") (name "OUT14_N") (class "Default")
      (node (ref "X-SOUTH") (pin "87") (pinfunction "87_87") (pintype "bidirectional"))
    )
    (net (code "102") (name "OUT14_P") (class "Default")
      (node (ref "X-SOUTH") (pin "85") (pinfunction "85_85") (pintype "bidirectional"))
    )
    (net (code "103") (name "OUT15_N") (class "Default")
      (node (ref "X-SOUTH") (pin "81") (pinfunction "81_81") (pintype "bidirectional"))
    )
    (net (code "104") (name "OUT15_P") (class "Default")
      (node (ref "X-SOUTH") (pin "79") (pinfunction "79_79") (pintype "bidirectional"))
    )
    (net (code "105") (name "OUT16_N") (class "Default")
      (node (ref "X-SOUTH") (pin "78") (pinfunction "78_78") (pintype "bidirectional"))
    )
    (net (code "106") (name "OUT16_P") (class "Default")
      (node (ref "X-SOUTH") (pin "76") (pinfunction "76_76") (pintype "bidirectional"))
    )
    (net (code "107") (name "OUT17_N") (class "Default")
      (node (ref "X-SOUTH") (pin "75") (pinfunction "75_75") (pintype "bidirectional"))
    )
    (net (code "108") (name "OUT17_P") (class "Default")
      (node (ref "X-SOUTH") (pin "73") (pinfunction "73_73") (pintype "bidirectional"))
    )
    (net (code "109") (name "OUT18_N") (class "Default")
      (node (ref "X-SOUTH") (pin "72") (pinfunction "72_72") (pintype "bidirectional"))
    )
    (net (code "110") (name "OUT18_P") (class "Default")
      (node (ref "X-SOUTH") (pin "70") (pinfunction "70_70") (pintype "bidirectional"))
    )
    (net (code "111") (name "OUT19_N") (class "Default")
      (node (ref "X-SOUTH") (pin "66") (pinfunction "66_66") (pintype "bidirectional"))
    )
    (net (code "112") (name "OUT19_P") (class "Default")
      (node (ref "X-SOUTH") (pin "64") (pinfunction "64_64") (pintype "bidirectional"))
    )
    (net (code "113") (name "OUT20_N") (class "Default")
      (node (ref "X-SOUTH") (pin "69") (pinfunction "69_69") (pintype "bidirectional"))
    )
    (net (code "114") (name "OUT20_P") (class "Default")
      (node (ref "X-SOUTH") (pin "67") (pinfunction "67_67") (pintype "bidirectional"))
    )
    (net (code "115") (name "OUT21_N") (class "Default")
      (node (ref "X-SOUTH") (pin "63") (pinfunction "63_63") (pintype "bidirectional"))
    )
    (net (code "116") (name "OUT21_P") (class "Default")
      (node (ref "X-SOUTH") (pin "61") (pinfunction "61_61") (pintype "bidirectional"))
    )
    (net (code "117") (name "OUT22_N") (class "Default")
      (node (ref "X-SOUTH") (pin "60") (pinfunction "60_60") (pintype "bidirectional"))
    )
    (net (code "118") (name "OUT22_P") (class "Default")
      (node (ref "X-SOUTH") (pin "58") (pinfunction "58_58") (pintype "bidirectional"))
    )
    (net (code "119") (name "OUT23_N") (class "Default")
      (node (ref "X-SOUTH") (pin "54") (pinfunction "54_54") (pintype "bidirectional"))
    )
    (net (code "120") (name "OUT23_P") (class "Default")
      (node (ref "X-SOUTH") (pin "52") (pinfunction "52_52") (pintype "bidirectional"))
    )
    (net (code "121") (name "OUT24_N") (class "Default")
      (node (ref "X-SOUTH") (pin "51") (pinfunction "51_51") (pintype "bidirectional"))
    )
    (net (code "122") (name "OUT24_P") (class "Default")
      (node (ref "X-SOUTH") (pin "49") (pinfunction "49_49") (pintype "bidirectional"))
    )
    (net (code "123") (name "OUT25_N") (class "Default")
      (node (ref "X-SOUTH") (pin "57") (pinfunction "57_57") (pintype "bidirectional"))
    )
    (net (code "124") (name "OUT25_P") (class "Default")
      (node (ref "X-SOUTH") (pin "55") (pinfunction "55_55") (pintype "bidirectional"))
    )
    (net (code "125") (name "OUT26_N") (class "Default")
      (node (ref "X-SOUTH") (pin "48") (pinfunction "48_48") (pintype "bidirectional"))
    )
    (net (code "126") (name "OUT26_P") (class "Default")
      (node (ref "X-SOUTH") (pin "46") (pinfunction "46_46") (pintype "bidirectional"))
    )
    (net (code "127") (name "OUT27_N") (class "Default")
      (node (ref "X-SOUTH") (pin "39") (pinfunction "39_39") (pintype "bidirectional"))
    )
    (net (code "128") (name "OUT27_P") (class "Default")
      (node (ref "X-SOUTH") (pin "37") (pinfunction "37_37") (pintype "bidirectional"))
    )
    (net (code "129") (name "OUT28_N") (class "Default")
      (node (ref "X-SOUTH") (pin "45") (pinfunction "45_45") (pintype "bidirectional"))
    )
    (net (code "130") (name "OUT28_P") (class "Default")
      (node (ref "X-SOUTH") (pin "43") (pinfunction "43_43") (pintype "bidirectional"))
    )
    (net (code "131") (name "OUT29_N") (class "Default")
      (node (ref "X-SOUTH") (pin "42") (pinfunction "42_42") (pintype "bidirectional"))
    )
    (net (code "132") (name "OUT29_P") (class "Default")
      (node (ref "X-SOUTH") (pin "40") (pinfunction "40_40") (pintype "bidirectional"))
    )
    (net (code "133") (name "OUT30_N") (class "Default")
      (node (ref "X-SOUTH") (pin "33") (pinfunction "33_33") (pintype "bidirectional"))
    )
    (net (code "134") (name "OUT30_P") (class "Default")
      (node (ref "X-SOUTH") (pin "31") (pinfunction "31_31") (pintype "bidirectional"))
    )
    (net (code "135") (name "OUT31_N") (class "Default")
      (node (ref "X-SOUTH") (pin "36") (pinfunction "36_36") (pintype "bidirectional"))
    )
    (net (code "136") (name "OUT31_P") (class "Default")
      (node (ref "X-SOUTH") (pin "34") (pinfunction "34_34") (pintype "bidirectional"))
    )
    (net (code "137") (name "OUT32_N") (class "Default")
      (node (ref "X-SOUTH") (pin "27") (pinfunction "27_27") (pintype "bidirectional"))
    )
    (net (code "138") (name "OUT32_P") (class "Default")
      (node (ref "X-SOUTH") (pin "25") (pinfunction "25_25") (pintype "bidirectional"))
    )
    (net (code "139") (name "OUT33_N") (class "Default")
      (node (ref "X-NORTH") (pin "19") (pinfunction "19_19") (pintype "bidirectional"))
    )
    (net (code "140") (name "OUT33_P") (class "Default")
      (node (ref "X-NORTH") (pin "21") (pinfunction "21_21") (pintype "bidirectional"))
    )
    (net (code "141") (name "OUT34_N") (class "Default")
      (node (ref "X-NORTH") (pin "28") (pinfunction "28_28") (pintype "bidirectional"))
    )
    (net (code "142") (name "OUT34_P") (class "Default")
      (node (ref "X-NORTH") (pin "30") (pinfunction "30_30") (pintype "bidirectional"))
    )
    (net (code "143") (name "OUT35_N") (class "Default")
      (node (ref "X-NORTH") (pin "25") (pinfunction "25_25") (pintype "bidirectional"))
    )
    (net (code "144") (name "OUT35_P") (class "Default")
      (node (ref "X-NORTH") (pin "27") (pinfunction "27_27") (pintype "bidirectional"))
    )
    (net (code "145") (name "OUT36_N") (class "Default")
      (node (ref "X-NORTH") (pin "34") (pinfunction "34_34") (pintype "bidirectional"))
    )
    (net (code "146") (name "OUT36_P") (class "Default")
      (node (ref "X-NORTH") (pin "36") (pinfunction "36_36") (pintype "bidirectional"))
    )
    (net (code "147") (name "OUT37_N") (class "Default")
      (node (ref "X-NORTH") (pin "31") (pinfunction "31_31") (pintype "bidirectional"))
    )
    (net (code "148") (name "OUT37_P") (class "Default")
      (node (ref "X-NORTH") (pin "33") (pinfunction "33_33") (pintype "bidirectional"))
    )
    (net (code "149") (name "OUT38_N") (class "Default")
      (node (ref "X-NORTH") (pin "37") (pinfunction "37_37") (pintype "bidirectional"))
    )
    (net (code "150") (name "OUT38_P") (class "Default")
      (node (ref "X-NORTH") (pin "39") (pinfunction "39_39") (pintype "bidirectional"))
    )
    (net (code "151") (name "OUT39_N") (class "Default")
      (node (ref "X-NORTH") (pin "40") (pinfunction "40_40") (pintype "bidirectional"))
    )
    (net (code "152") (name "OUT39_P") (class "Default")
      (node (ref "X-NORTH") (pin "42") (pinfunction "42_42") (pintype "bidirectional"))
    )
    (net (code "153") (name "OUT40_N") (class "Default")
      (node (ref "X-NORTH") (pin "43") (pinfunction "43_43") (pintype "bidirectional"))
    )
    (net (code "154") (name "OUT40_P") (class "Default")
      (node (ref "X-NORTH") (pin "45") (pinfunction "45_45") (pintype "bidirectional"))
    )
    (net (code "155") (name "OUT41_N") (class "Default")
      (node (ref "X-NORTH") (pin "46") (pinfunction "46_46") (pintype "bidirectional"))
    )
    (net (code "156") (name "OUT41_P") (class "Default")
      (node (ref "X-NORTH") (pin "48") (pinfunction "48_48") (pintype "bidirectional"))
    )
    (net (code "157") (name "OUT42_N") (class "Default")
      (node (ref "X-NORTH") (pin "49") (pinfunction "49_49") (pintype "bidirectional"))
    )
    (net (code "158") (name "OUT42_P") (class "Default")
      (node (ref "X-NORTH") (pin "51") (pinfunction "51_51") (pintype "bidirectional"))
    )
    (net (code "159") (name "OUT43_N") (class "Default")
      (node (ref "X-NORTH") (pin "52") (pinfunction "52_52") (pintype "bidirectional"))
    )
    (net (code "160") (name "OUT43_P") (class "Default")
      (node (ref "X-NORTH") (pin "54") (pinfunction "54_54") (pintype "bidirectional"))
    )
    (net (code "161") (name "OUT44_N") (class "Default")
      (node (ref "X-NORTH") (pin "55") (pinfunction "55_55") (pintype "bidirectional"))
    )
    (net (code "162") (name "OUT44_P") (class "Default")
      (node (ref "X-NORTH") (pin "57") (pinfunction "57_57") (pintype "bidirectional"))
    )
    (net (code "163") (name "OUT45_N") (class "Default")
      (node (ref "X-NORTH") (pin "58") (pinfunction "58_58") (pintype "bidirectional"))
    )
    (net (code "164") (name "OUT45_P") (class "Default")
      (node (ref "X-NORTH") (pin "60") (pinfunction "60_60") (pintype "bidirectional"))
    )
    (net (code "165") (name "OUT46_N") (class "Default")
      (node (ref "X-NORTH") (pin "61") (pinfunction "61_61") (pintype "bidirectional"))
    )
    (net (code "166") (name "OUT46_P") (class "Default")
      (node (ref "X-NORTH") (pin "63") (pinfunction "63_63") (pintype "bidirectional"))
    )
    (net (code "167") (name "OUT47_N") (class "Default")
      (node (ref "X-NORTH") (pin "64") (pinfunction "64_64") (pintype "bidirectional"))
    )
    (net (code "168") (name "OUT47_P") (class "Default")
      (node (ref "X-NORTH") (pin "66") (pinfunction "66_66") (pintype "bidirectional"))
    )
    (net (code "169") (name "OUT48_N") (class "Default")
      (node (ref "X-NORTH") (pin "67") (pinfunction "67_67") (pintype "bidirectional"))
    )
    (net (code "170") (name "OUT48_P") (class "Default")
      (node (ref "X-NORTH") (pin "69") (pinfunction "69_69") (pintype "bidirectional"))
    )
    (net (code "171") (name "OUT49_N") (class "Default")
      (node (ref "X-NORTH") (pin "73") (pinfunction "73_73") (pintype "bidirectional"))
    )
    (net (code "172") (name "OUT49_P") (class "Default")
      (node (ref "X-NORTH") (pin "75") (pinfunction "75_75") (pintype "bidirectional"))
    )
    (net (code "173") (name "OUT50_N") (class "Default")
      (node (ref "X-NORTH") (pin "70") (pinfunction "70_70") (pintype "bidirectional"))
    )
    (net (code "174") (name "OUT50_P") (class "Default")
      (node (ref "X-NORTH") (pin "72") (pinfunction "72_72") (pintype "bidirectional"))
    )
    (net (code "175") (name "OUT51_N") (class "Default")
      (node (ref "X-NORTH") (pin "79") (pinfunction "79_79") (pintype "bidirectional"))
    )
    (net (code "176") (name "OUT51_P") (class "Default")
      (node (ref "X-NORTH") (pin "81") (pinfunction "81_81") (pintype "bidirectional"))
    )
    (net (code "177") (name "OUT52_N") (class "Default")
      (node (ref "X-NORTH") (pin "76") (pinfunction "76_76") (pintype "bidirectional"))
    )
    (net (code "178") (name "OUT52_P") (class "Default")
      (node (ref "X-NORTH") (pin "78") (pinfunction "78_78") (pintype "bidirectional"))
    )
    (net (code "179") (name "OUT53_N") (class "Default")
      (node (ref "X-NORTH") (pin "85") (pinfunction "85_85") (pintype "bidirectional"))
    )
    (net (code "180") (name "OUT53_P") (class "Default")
      (node (ref "X-NORTH") (pin "87") (pinfunction "87_87") (pintype "bidirectional"))
    )
    (net (code "181") (name "OUT54_N") (class "Default")
      (node (ref "X-NORTH") (pin "82") (pinfunction "82_82") (pintype "bidirectional"))
    )
    (net (code "182") (name "OUT54_P") (class "Default")
      (node (ref "X-NORTH") (pin "84") (pinfunction "84_84") (pintype "bidirectional"))
    )
    (net (code "183") (name "OUT55_N") (class "Default")
      (node (ref "X-NORTH") (pin "91") (pinfunction "91_91") (pintype "bidirectional"))
    )
    (net (code "184") (name "OUT55_P") (class "Default")
      (node (ref "X-NORTH") (pin "93") (pinfunction "93_93") (pintype "bidirectional"))
    )
    (net (code "185") (name "OUT56_N") (class "Default")
      (node (ref "X-NORTH") (pin "88") (pinfunction "88_88") (pintype "bidirectional"))
    )
    (net (code "186") (name "OUT56_P") (class "Default")
      (node (ref "X-NORTH") (pin "90") (pinfunction "90_90") (pintype "bidirectional"))
    )
    (net (code "187") (name "OUT57_N") (class "Default")
      (node (ref "X-NORTH") (pin "97") (pinfunction "97_97") (pintype "bidirectional"))
    )
    (net (code "188") (name "OUT57_P") (class "Default")
      (node (ref "X-NORTH") (pin "99") (pinfunction "99_99") (pintype "bidirectional"))
    )
    (net (code "189") (name "OUT58_N") (class "Default")
      (node (ref "X-NORTH") (pin "94") (pinfunction "94_94") (pintype "bidirectional"))
    )
    (net (code "190") (name "OUT58_P") (class "Default")
      (node (ref "X-NORTH") (pin "96") (pinfunction "96_96") (pintype "bidirectional"))
    )
    (net (code "191") (name "OUT59_N") (class "Default")
      (node (ref "X-NORTH") (pin "103") (pinfunction "103_103") (pintype "bidirectional"))
    )
    (net (code "192") (name "OUT59_P") (class "Default")
      (node (ref "X-NORTH") (pin "105") (pinfunction "105_105") (pintype "bidirectional"))
    )
    (net (code "193") (name "OUT60_N") (class "Default")
      (node (ref "X-NORTH") (pin "109") (pinfunction "109_109") (pintype "bidirectional"))
    )
    (net (code "194") (name "OUT60_P") (class "Default")
      (node (ref "X-NORTH") (pin "111") (pinfunction "111_111") (pintype "bidirectional"))
    )
    (net (code "195") (name "OUT61_N") (class "Default")
      (node (ref "X-NORTH") (pin "100") (pinfunction "100_100") (pintype "bidirectional"))
    )
    (net (code "196") (name "OUT61_P") (class "Default")
      (node (ref "X-NORTH") (pin "102") (pinfunction "102_102") (pintype "bidirectional"))
    )
    (net (code "197") (name "OUT62_N") (class "Default")
      (node (ref "X-NORTH") (pin "115") (pinfunction "115_115") (pintype "bidirectional"))
    )
    (net (code "198") (name "OUT62_P") (class "Default")
      (node (ref "X-NORTH") (pin "117") (pinfunction "117_117") (pintype "bidirectional"))
    )
    (net (code "199") (name "OUT63_N") (class "Default")
      (node (ref "X-NORTH") (pin "106") (pinfunction "106_106") (pintype "bidirectional"))
    )
    (net (code "200") (name "OUT63_P") (class "Default")
      (node (ref "X-NORTH") (pin "108") (pinfunction "108_108") (pintype "bidirectional"))
    )
    (net (code "201") (name "OUT64_N") (class "Default")
      (node (ref "X-NORTH") (pin "112") (pinfunction "112_112") (pintype "bidirectional"))
    )
    (net (code "202") (name "OUT64_P") (class "Default")
      (node (ref "X-NORTH") (pin "114") (pinfunction "114_114") (pintype "bidirectional"))
    )
    (net (code "203") (name "OUTCLK_N") (class "Default")
      (node (ref "X-NORTH") (pin "16") (pinfunction "16_16") (pintype "bidirectional"))
    )
    (net (code "204") (name "OUTCLK_P") (class "Default")
      (node (ref "X-NORTH") (pin "18") (pinfunction "18_18") (pintype "bidirectional"))
    )
    (net (code "205") (name "OUTCTR_N") (class "Default")
      (node (ref "X-SOUTH") (pin "126") (pinfunction "126_126") (pintype "bidirectional"))
    )
    (net (code "206") (name "OUTCTR_P") (class "Default")
      (node (ref "X-SOUTH") (pin "124") (pinfunction "124_124") (pintype "bidirectional"))
    )
    (net (code "207") (name "S00_N") (class "Default")
      (node (ref "X-SOUTH") (pin "15") (pinfunction "15_15") (pintype "bidirectional"))
    )
    (net (code "208") (name "S00_P") (class "Default")
      (node (ref "X-SOUTH") (pin "13") (pinfunction "13_13") (pintype "bidirectional"))
    )
    (net (code "209") (name "S01_N") (class "Default")
      (node (ref "X-SOUTH") (pin "18") (pinfunction "18_18") (pintype "bidirectional"))
    )
    (net (code "210") (name "S01_P") (class "Default")
      (node (ref "X-SOUTH") (pin "16") (pinfunction "16_16") (pintype "bidirectional"))
    )
    (net (code "211") (name "S02_N") (class "Default")
      (node (ref "X-SOUTH") (pin "21") (pinfunction "21_21") (pintype "bidirectional"))
    )
    (net (code "212") (name "S02_P") (class "Default")
      (node (ref "X-SOUTH") (pin "19") (pinfunction "19_19") (pintype "bidirectional"))
    )
    (net (code "213") (name "S03_N") (class "Default")
      (node (ref "X-SOUTH") (pin "24") (pinfunction "24_24") (pintype "bidirectional"))
    )
    (net (code "214") (name "S03_P") (class "Default")
      (node (ref "X-SOUTH") (pin "22") (pinfunction "22_22") (pintype "bidirectional"))
    )
    (net (code "215") (name "S05_N") (class "Default")
      (node (ref "X-SOUTH") (pin "30") (pinfunction "30_30") (pintype "bidirectional"))
    )
    (net (code "216") (name "S05_P") (class "Default")
      (node (ref "X-SOUTH") (pin "28") (pinfunction "28_28") (pintype "bidirectional"))
    )
    (net (code "217") (name "S38_N") (class "Default")
      (node (ref "X-SOUTH") (pin "129") (pinfunction "129_129") (pintype "bidirectional"))
    )
    (net (code "218") (name "S38_P") (class "Default")
      (node (ref "X-SOUTH") (pin "127") (pinfunction "127_127") (pintype "bidirectional"))
    )
    (net (code "219") (name "S39_P") (class "Default")
      (node (ref "X-SOUTH") (pin "130") (pinfunction "130_130") (pintype "bidirectional"))
    )
    (net (code "220") (name "SPI_EN") (class "Default")
      (node (ref "X-NORTH") (pin "120") (pinfunction "120_120") (pintype "bidirectional"))
    )
    (net (code "221") (name "SYS_RES_N") (class "Default")
      (node (ref "X-NORTH") (pin "126") (pinfunction "126_126") (pintype "bidirectional"))
    )
    (net (code "222") (name "S_CHK_V") (class "Default")
      (node (ref "X-EAST") (pin "112") (pinfunction "112_112") (pintype "bidirectional"))
      (node (ref "X-EAST") (pin "114") (pinfunction "114_114") (pintype "bidirectional"))
      (node (ref "X-SOUTH") (pin "7") (pinfunction "7_7") (pintype "bidirectional"))
      (node (ref "X-SOUTH") (pin "9") (pinfunction "9_9") (pintype "bidirectional"))
    )
    (net (code "223") (name "S_I2C_V") (class "Default")
      (node (ref "X-SOUTH") (pin "136") (pinfunction "136_136") (pintype "bidirectional"))
      (node (ref "X-SOUTH") (pin "138") (pinfunction "138_138") (pintype "bidirectional"))
      (node (ref "X-WEST") (pin "7") (pinfunction "7_7") (pintype "bidirectional"))
      (node (ref "X-WEST") (pin "9") (pinfunction "9_9") (pintype "bidirectional"))
    )
    (net (code "224") (name "S_SCK") (class "Default")
      (node (ref "X-SOUTH") (pin "143") (pinfunction "143_143") (pintype "bidirectional"))
      (node (ref "X-WEST") (pin "2") (pinfunction "2_2") (pintype "bidirectional"))
    )
    (net (code "225") (name "S_SCL") (class "Default")
      (node (ref "X-SOUTH") (pin "144") (pinfunction "144_144") (pintype "bidirectional"))
      (node (ref "X-WEST") (pin "1") (pinfunction "1_1") (pintype "bidirectional"))
    )
    (net (code "226") (name "S_SDA") (class "Default")
      (node (ref "X-SOUTH") (pin "142") (pinfunction "142_142") (pintype "bidirectional"))
      (node (ref "X-WEST") (pin "3") (pinfunction "3_3") (pintype "bidirectional"))
    )
    (net (code "227") (name "S_SDI") (class "Default")
      (node (ref "X-SOUTH") (pin "139") (pinfunction "139_139") (pintype "bidirectional"))
      (node (ref "X-WEST") (pin "6") (pinfunction "6_6") (pintype "bidirectional"))
    )
    (net (code "228") (name "S_SDO") (class "Default")
      (node (ref "X-SOUTH") (pin "141") (pinfunction "141_141") (pintype "bidirectional"))
      (node (ref "X-WEST") (pin "4") (pinfunction "4_4") (pintype "bidirectional"))
    )
    (net (code "229") (name "S_SPI_V") (class "Default")
      (node (ref "X-SOUTH") (pin "133") (pinfunction "133_133") (pintype "bidirectional"))
      (node (ref "X-SOUTH") (pin "135") (pinfunction "135_135") (pintype "bidirectional"))
      (node (ref "X-WEST") (pin "10") (pinfunction "10_10") (pintype "bidirectional"))
      (node (ref "X-WEST") (pin "8") (pinfunction "8_8") (pintype "bidirectional"))
    )
    (net (code "230") (name "S_VE") (class "Default")
      (node (ref "X-EAST") (pin "61") (pinfunction "61_61") (pintype "bidirectional"))
      (node (ref "X-EAST") (pin "63") (pinfunction "63_63") (pintype "bidirectional"))
      (node (ref "X-EAST") (pin "65") (pinfunction "65_65") (pintype "bidirectional"))
      (node (ref "X-EAST") (pin "67") (pinfunction "67_67") (pintype "bidirectional"))
      (node (ref "X-EAST") (pin "69") (pinfunction "69_69") (pintype "bidirectional"))
      (node (ref "X-EAST") (pin "71") (pinfunction "71_71") (pintype "bidirectional"))
      (node (ref "X-SOUTH") (pin "14") (pinfunction "14_14") (pintype "bidirectional"))
      (node (ref "X-SOUTH") (pin "20") (pinfunction "20_20") (pintype "bidirectional"))
      (node (ref "X-SOUTH") (pin "26") (pinfunction "26_26") (pintype "bidirectional"))
      (node (ref "X-SOUTH") (pin "32") (pinfunction "32_32") (pintype "bidirectional"))
      (node (ref "X-SOUTH") (pin "38") (pinfunction "38_38") (pintype "bidirectional"))
      (node (ref "X-SOUTH") (pin "44") (pinfunction "44_44") (pintype "bidirectional"))
    )
    (net (code "231") (name "S_VE_CV") (class "Default")
      (node (ref "X-EAST") (pin "120") (pinfunction "120_120") (pintype "bidirectional"))
      (node (ref "X-SOUTH") (pin "1") (pinfunction "1_1") (pintype "bidirectional"))
    )
    (net (code "232") (name "S_VE_OV") (class "Default")
      (node (ref "X-EAST") (pin "119") (pinfunction "119_119") (pintype "bidirectional"))
      (node (ref "X-SOUTH") (pin "2") (pinfunction "2_2") (pintype "bidirectional"))
    )
    (net (code "233") (name "S_VE_UV") (class "Default")
      (node (ref "X-EAST") (pin "109") (pinfunction "109_109") (pintype "bidirectional"))
      (node (ref "X-SOUTH") (pin "8") (pinfunction "8_8") (pintype "bidirectional"))
    )
    (net (code "234") (name "S_VS") (class "Default")
      (node (ref "X-EAST") (pin "52") (pinfunction "52_52") (pintype "bidirectional"))
      (node (ref "X-EAST") (pin "54") (pinfunction "54_54") (pintype "bidirectional"))
      (node (ref "X-EAST") (pin "56") (pinfunction "56_56") (pintype "bidirectional"))
      (node (ref "X-EAST") (pin "58") (pinfunction "58_58") (pintype "bidirectional"))
      (node (ref "X-EAST") (pin "60") (pinfunction "60_60") (pintype "bidirectional"))
      (node (ref "X-EAST") (pin "62") (pinfunction "62_62") (pintype "bidirectional"))
      (node (ref "X-EAST") (pin "64") (pinfunction "64_64") (pintype "bidirectional"))
      (node (ref "X-EAST") (pin "66") (pinfunction "66_66") (pintype "bidirectional"))
      (node (ref "X-EAST") (pin "68") (pinfunction "68_68") (pintype "bidirectional"))
      (node (ref "X-EAST") (pin "70") (pinfunction "70_70") (pintype "bidirectional"))
      (node (ref "X-SOUTH") (pin "50") (pinfunction "50_50") (pintype "bidirectional"))
      (node (ref "X-SOUTH") (pin "56") (pinfunction "56_56") (pintype "bidirectional"))
      (node (ref "X-SOUTH") (pin "62") (pinfunction "62_62") (pintype "bidirectional"))
      (node (ref "X-SOUTH") (pin "68") (pinfunction "68_68") (pintype "bidirectional"))
      (node (ref "X-SOUTH") (pin "74") (pinfunction "74_74") (pintype "bidirectional"))
      (node (ref "X-SOUTH") (pin "80") (pinfunction "80_80") (pintype "bidirectional"))
      (node (ref "X-SOUTH") (pin "86") (pinfunction "86_86") (pintype "bidirectional"))
      (node (ref "X-SOUTH") (pin "92") (pinfunction "92_92") (pintype "bidirectional"))
      (node (ref "X-SOUTH") (pin "98") (pinfunction "98_98") (pintype "bidirectional"))
    )
    (net (code "235") (name "S_VS_CV") (class "Default")
      (node (ref "X-EAST") (pin "118") (pinfunction "118_118") (pintype "bidirectional"))
      (node (ref "X-SOUTH") (pin "3") (pinfunction "3_3") (pintype "bidirectional"))
    )
    (net (code "236") (name "S_VS_OV") (class "Default")
      (node (ref "X-EAST") (pin "117") (pinfunction "117_117") (pintype "bidirectional"))
      (node (ref "X-SOUTH") (pin "4") (pinfunction "4_4") (pintype "bidirectional"))
    )
    (net (code "237") (name "S_VS_UV") (class "Default")
      (node (ref "X-EAST") (pin "107") (pinfunction "107_107") (pintype "bidirectional"))
      (node (ref "X-SOUTH") (pin "10") (pinfunction "10_10") (pintype "bidirectional"))
    )
    (net (code "238") (name "S_VW") (class "Default")
      (node (ref "X-SOUTH") (pin "104") (pinfunction "104_104") (pintype "bidirectional"))
      (node (ref "X-SOUTH") (pin "110") (pinfunction "110_110") (pintype "bidirectional"))
      (node (ref "X-SOUTH") (pin "116") (pinfunction "116_116") (pintype "bidirectional"))
      (node (ref "X-SOUTH") (pin "122") (pinfunction "122_122") (pintype "bidirectional"))
      (node (ref "X-SOUTH") (pin "128") (pinfunction "128_128") (pintype "bidirectional"))
      (node (ref "X-SOUTH") (pin "134") (pinfunction "134_134") (pintype "bidirectional"))
      (node (ref "X-WEST") (pin "49") (pinfunction "49_49") (pintype "bidirectional"))
      (node (ref "X-WEST") (pin "51") (pinfunction "51_51") (pintype "bidirectional"))
      (node (ref "X-WEST") (pin "53") (pinfunction "53_53") (pintype "bidirectional"))
      (node (ref "X-WEST") (pin "55") (pinfunction "55_55") (pintype "bidirectional"))
      (node (ref "X-WEST") (pin "57") (pinfunction "57_57") (pintype "bidirectional"))
      (node (ref "X-WEST") (pin "59") (pinfunction "59_59") (pintype "bidirectional"))
    )
    (net (code "239") (name "S_VW_CV") (class "Default")
      (node (ref "X-EAST") (pin "116") (pinfunction "116_116") (pintype "bidirectional"))
      (node (ref "X-SOUTH") (pin "5") (pinfunction "5_5") (pintype "bidirectional"))
    )
    (net (code "240") (name "S_VW_OV") (class "Default")
      (node (ref "X-EAST") (pin "115") (pinfunction "115_115") (pintype "bidirectional"))
      (node (ref "X-SOUTH") (pin "6") (pinfunction "6_6") (pintype "bidirectional"))
    )
    (net (code "241") (name "S_VW_UV") (class "Default")
      (node (ref "X-EAST") (pin "105") (pinfunction "105_105") (pintype "bidirectional"))
      (node (ref "X-SOUTH") (pin "12") (pinfunction "12_12") (pintype "bidirectional"))
    )
    (net (code "242") (name "TCK") (class "Default")
      (node (ref "X-EAST") (pin "12") (pinfunction "12_12") (pintype "bidirectional"))
    )
    (net (code "243") (name "TDI") (class "Default")
      (node (ref "X-EAST") (pin "16") (pinfunction "16_16") (pintype "bidirectional"))
    )
    (net (code "244") (name "TDIG1") (class "Default")
      (node (ref "X-NORTH") (pin "124") (pinfunction "124_124") (pintype "bidirectional"))
    )
    (net (code "245") (name "TDIG2") (class "Default")
      (node (ref "X-NORTH") (pin "129") (pinfunction "129_129") (pintype "bidirectional"))
    )
    (net (code "246") (name "TDO") (class "Default")
      (node (ref "X-EAST") (pin "18") (pinfunction "18_18") (pintype "bidirectional"))
    )
    (net (code "247") (name "TMS") (class "Default")
      (node (ref "X-EAST") (pin "14") (pinfunction "14_14") (pintype "bidirectional"))
    )
    (net (code "248") (name "T_EXP1") (class "Default")
      (node (ref "X-NORTH") (pin "132") (pinfunction "132_132") (pintype "bidirectional"))
    )
    (net (code "249") (name "T_EXP2") (class "Default")
      (node (ref "X-NORTH") (pin "118") (pinfunction "118_118") (pintype "bidirectional"))
    )
    (net (code "250") (name "VREF_EN") (class "Default")
      (node (ref "X-SOUTH") (pin "132") (pinfunction "132_132") (pintype "bidirectional"))
    )
    (net (code "251") (name "W00_N") (class "Default")
      (node (ref "X-WEST") (pin "22") (pinfunction "22_22") (pintype "bidirectional"))
    )
    (net (code "252") (name "W00_P") (class "Default")
      (node (ref "X-WEST") (pin "24") (pinfunction "24_24") (pintype "bidirectional"))
    )
    (net (code "253") (name "W01_N") (class "Default")
      (node (ref "X-WEST") (pin "25") (pinfunction "25_25") (pintype "bidirectional"))
    )
    (net (code "254") (name "W01_P") (class "Default")
      (node (ref "X-WEST") (pin "27") (pinfunction "27_27") (pintype "bidirectional"))
    )
    (net (code "255") (name "W02_N") (class "Default")
      (node (ref "X-WEST") (pin "28") (pinfunction "28_28") (pintype "bidirectional"))
    )
    (net (code "256") (name "W02_P") (class "Default")
      (node (ref "X-WEST") (pin "30") (pinfunction "30_30") (pintype "bidirectional"))
    )
    (net (code "257") (name "W03_N") (class "Default")
      (node (ref "X-WEST") (pin "31") (pinfunction "31_31") (pintype "bidirectional"))
    )
    (net (code "258") (name "W03_P") (class "Default")
      (node (ref "X-WEST") (pin "33") (pinfunction "33_33") (pintype "bidirectional"))
    )
    (net (code "259") (name "W04_N") (class "Default")
      (node (ref "X-WEST") (pin "34") (pinfunction "34_34") (pintype "bidirectional"))
    )
    (net (code "260") (name "W04_P") (class "Default")
      (node (ref "X-WEST") (pin "36") (pinfunction "36_36") (pintype "bidirectional"))
    )
    (net (code "261") (name "W05_N") (class "Default")
      (node (ref "X-WEST") (pin "37") (pinfunction "37_37") (pintype "bidirectional"))
    )
    (net (code "262") (name "W05_P") (class "Default")
      (node (ref "X-WEST") (pin "39") (pinfunction "39_39") (pintype "bidirectional"))
    )
    (net (code "263") (name "W06_N") (class "Default")
      (node (ref "X-WEST") (pin "40") (pinfunction "40_40") (pintype "bidirectional"))
    )
    (net (code "264") (name "W06_P") (class "Default")
      (node (ref "X-WEST") (pin "42") (pinfunction "42_42") (pintype "bidirectional"))
    )
    (net (code "265") (name "W07_N") (class "Default")
      (node (ref "X-WEST") (pin "43") (pinfunction "43_43") (pintype "bidirectional"))
    )
    (net (code "266") (name "W07_P") (class "Default")
      (node (ref "X-WEST") (pin "45") (pinfunction "45_45") (pintype "bidirectional"))
    )
    (net (code "267") (name "W08_N") (class "Default")
      (node (ref "X-WEST") (pin "46") (pinfunction "46_46") (pintype "bidirectional"))
    )
    (net (code "268") (name "W08_P") (class "Default")
      (node (ref "X-WEST") (pin "48") (pinfunction "48_48") (pintype "bidirectional"))
    )
    (net (code "269") (name "W09_N") (class "Default")
      (node (ref "X-WEST") (pin "74") (pinfunction "74_74") (pintype "bidirectional"))
    )
    (net (code "270") (name "W09_P") (class "Default")
      (node (ref "X-WEST") (pin "76") (pinfunction "76_76") (pintype "bidirectional"))
    )
    (net (code "271") (name "W10_N") (class "Default")
      (node (ref "X-WEST") (pin "75") (pinfunction "75_75") (pintype "bidirectional"))
    )
    (net (code "272") (name "W10_P") (class "Default")
      (node (ref "X-WEST") (pin "77") (pinfunction "77_77") (pintype "bidirectional"))
    )
    (net (code "273") (name "W11_N") (class "Default")
      (node (ref "X-WEST") (pin "80") (pinfunction "80_80") (pintype "bidirectional"))
    )
    (net (code "274") (name "W11_P") (class "Default")
      (node (ref "X-WEST") (pin "82") (pinfunction "82_82") (pintype "bidirectional"))
    )
    (net (code "275") (name "W12_N") (class "Default")
      (node (ref "X-WEST") (pin "81") (pinfunction "81_81") (pintype "bidirectional"))
    )
    (net (code "276") (name "W12_P") (class "Default")
      (node (ref "X-WEST") (pin "83") (pinfunction "83_83") (pintype "bidirectional"))
    )
    (net (code "277") (name "W13_N") (class "Default")
      (node (ref "X-WEST") (pin "86") (pinfunction "86_86") (pintype "bidirectional"))
    )
    (net (code "278") (name "W13_P") (class "Default")
      (node (ref "X-WEST") (pin "88") (pinfunction "88_88") (pintype "bidirectional"))
    )
    (net (code "279") (name "W14_N") (class "Default")
      (node (ref "X-WEST") (pin "87") (pinfunction "87_87") (pintype "bidirectional"))
    )
    (net (code "280") (name "W14_P") (class "Default")
      (node (ref "X-WEST") (pin "89") (pinfunction "89_89") (pintype "bidirectional"))
    )
    (net (code "281") (name "W15_N") (class "Default")
      (node (ref "X-WEST") (pin "92") (pinfunction "92_92") (pintype "bidirectional"))
    )
    (net (code "282") (name "W15_P") (class "Default")
      (node (ref "X-WEST") (pin "94") (pinfunction "94_94") (pintype "bidirectional"))
    )
    (net (code "283") (name "W16_N") (class "Default")
      (node (ref "X-WEST") (pin "93") (pinfunction "93_93") (pintype "bidirectional"))
    )
    (net (code "284") (name "W16_P") (class "Default")
      (node (ref "X-WEST") (pin "95") (pinfunction "95_95") (pintype "bidirectional"))
    )
    (net (code "285") (name "W17_N") (class "Default")
      (node (ref "X-WEST") (pin "98") (pinfunction "98_98") (pintype "bidirectional"))
    )
    (net (code "286") (name "W17_P") (class "Default")
      (node (ref "X-WEST") (pin "100") (pinfunction "100_100") (pintype "bidirectional"))
    )
    (net (code "287") (name "W_EN") (class "Default")
      (node (ref "X-WEST") (pin "14") (pinfunction "14_14") (pintype "bidirectional"))
    )
    (net (code "288") (name "W_I2C_V") (class "Default")
      (node (ref "X-WEST") (pin "11") (pinfunction "11_11") (pintype "bidirectional"))
      (node (ref "X-WEST") (pin "13") (pinfunction "13_13") (pintype "bidirectional"))
    )
    (net (code "289") (name "W_SCK") (class "Default")
      (node (ref "X-WEST") (pin "12") (pinfunction "12_12") (pintype "bidirectional"))
    )
    (net (code "290") (name "W_SCL") (class "Default")
      (node (ref "X-WEST") (pin "15") (pinfunction "15_15") (pintype "bidirectional"))
    )
    (net (code "291") (name "W_SDA") (class "Default")
      (node (ref "X-WEST") (pin "17") (pinfunction "17_17") (pintype "bidirectional"))
    )
    (net (code "292") (name "W_SDI") (class "Default")
      (node (ref "X-WEST") (pin "16") (pinfunction "16_16") (pintype "bidirectional"))
    )
    (net (code "293") (name "W_SDI_V") (class "Default")
      (node (ref "X-WEST") (pin "19") (pinfunction "19_19") (pintype "bidirectional"))
      (node (ref "X-WEST") (pin "21") (pinfunction "21_21") (pintype "bidirectional"))
    )
    (net (code "294") (name "W_SDO") (class "Default")
      (node (ref "X-WEST") (pin "18") (pinfunction "18_18") (pintype "bidirectional"))
    )
    (net (code "295") (name "W_VW") (class "Default")
      (node (ref "X-WEST") (pin "101") (pinfunction "101_101") (pintype "bidirectional"))
      (node (ref "X-WEST") (pin "103") (pinfunction "103_103") (pintype "bidirectional"))
      (node (ref "X-WEST") (pin "104") (pinfunction "104_104") (pintype "bidirectional"))
      (node (ref "X-WEST") (pin "106") (pinfunction "106_106") (pintype "bidirectional"))
      (node (ref "X-WEST") (pin "108") (pinfunction "108_108") (pintype "bidirectional"))
      (node (ref "X-WEST") (pin "99") (pinfunction "99_99") (pintype "bidirectional"))
    )
    (net (code "296") (name "W_VW_CV") (class "Default")
      (node (ref "X-WEST") (pin "110") (pinfunction "110_110") (pintype "bidirectional"))
    )
    (net (code "297") (name "W_VW_OV") (class "Default")
      (node (ref "X-WEST") (pin "113") (pinfunction "113_113") (pintype "bidirectional"))
    )
    (net (code "298") (name "W_VW_UV") (class "Default")
      (node (ref "X-WEST") (pin "111") (pinfunction "111_111") (pintype "bidirectional"))
    )
    (net (code "299") (name "unconnected-(X-EAST-PadM1)") (class "Default")
      (node (ref "X-EAST") (pin "M1") (pinfunction "M1_M1") (pintype "bidirectional"))
    )
    (net (code "300") (name "unconnected-(X-EAST-PadM2)") (class "Default")
      (node (ref "X-EAST") (pin "M2") (pinfunction "M2_M2") (pintype "bidirectional"))
    )
    (net (code "301") (name "unconnected-(X-NORTH-PadM1)") (class "Default")
      (node (ref "X-NORTH") (pin "M1") (pinfunction "M1_M1") (pintype "bidirectional"))
    )
    (net (code "302") (name "unconnected-(X-NORTH-PadM2)") (class "Default")
      (node (ref "X-NORTH") (pin "M2") (pinfunction "M2_M2") (pintype "bidirectional"))
    )
    (net (code "303") (name "unconnected-(X-SOUTH-PadM1)") (class "Default")
      (node (ref "X-SOUTH") (pin "M1") (pinfunction "M1_M1") (pintype "bidirectional"))
    )
    (net (code "304") (name "unconnected-(X-SOUTH-PadM2)") (class "Default")
      (node (ref "X-SOUTH") (pin "M2") (pinfunction "M2_M2") (pintype "bidirectional"))
    )
    (net (code "305") (name "unconnected-(X-WEST-PadM1)") (class "Default")
      (node (ref "X-WEST") (pin "M1") (pinfunction "M1_M1") (pintype "bidirectional"))
    )
    (net (code "306") (name "unconnected-(X-WEST-PadM2)") (class "Default")
      (node (ref "X-WEST") (pin "M2") (pinfunction "M2_M2") (pintype "bidirectional"))
    )
  )
)
